# labwiz-module_t420.net
KiCad netlist of a schematic drawn in EAGLE
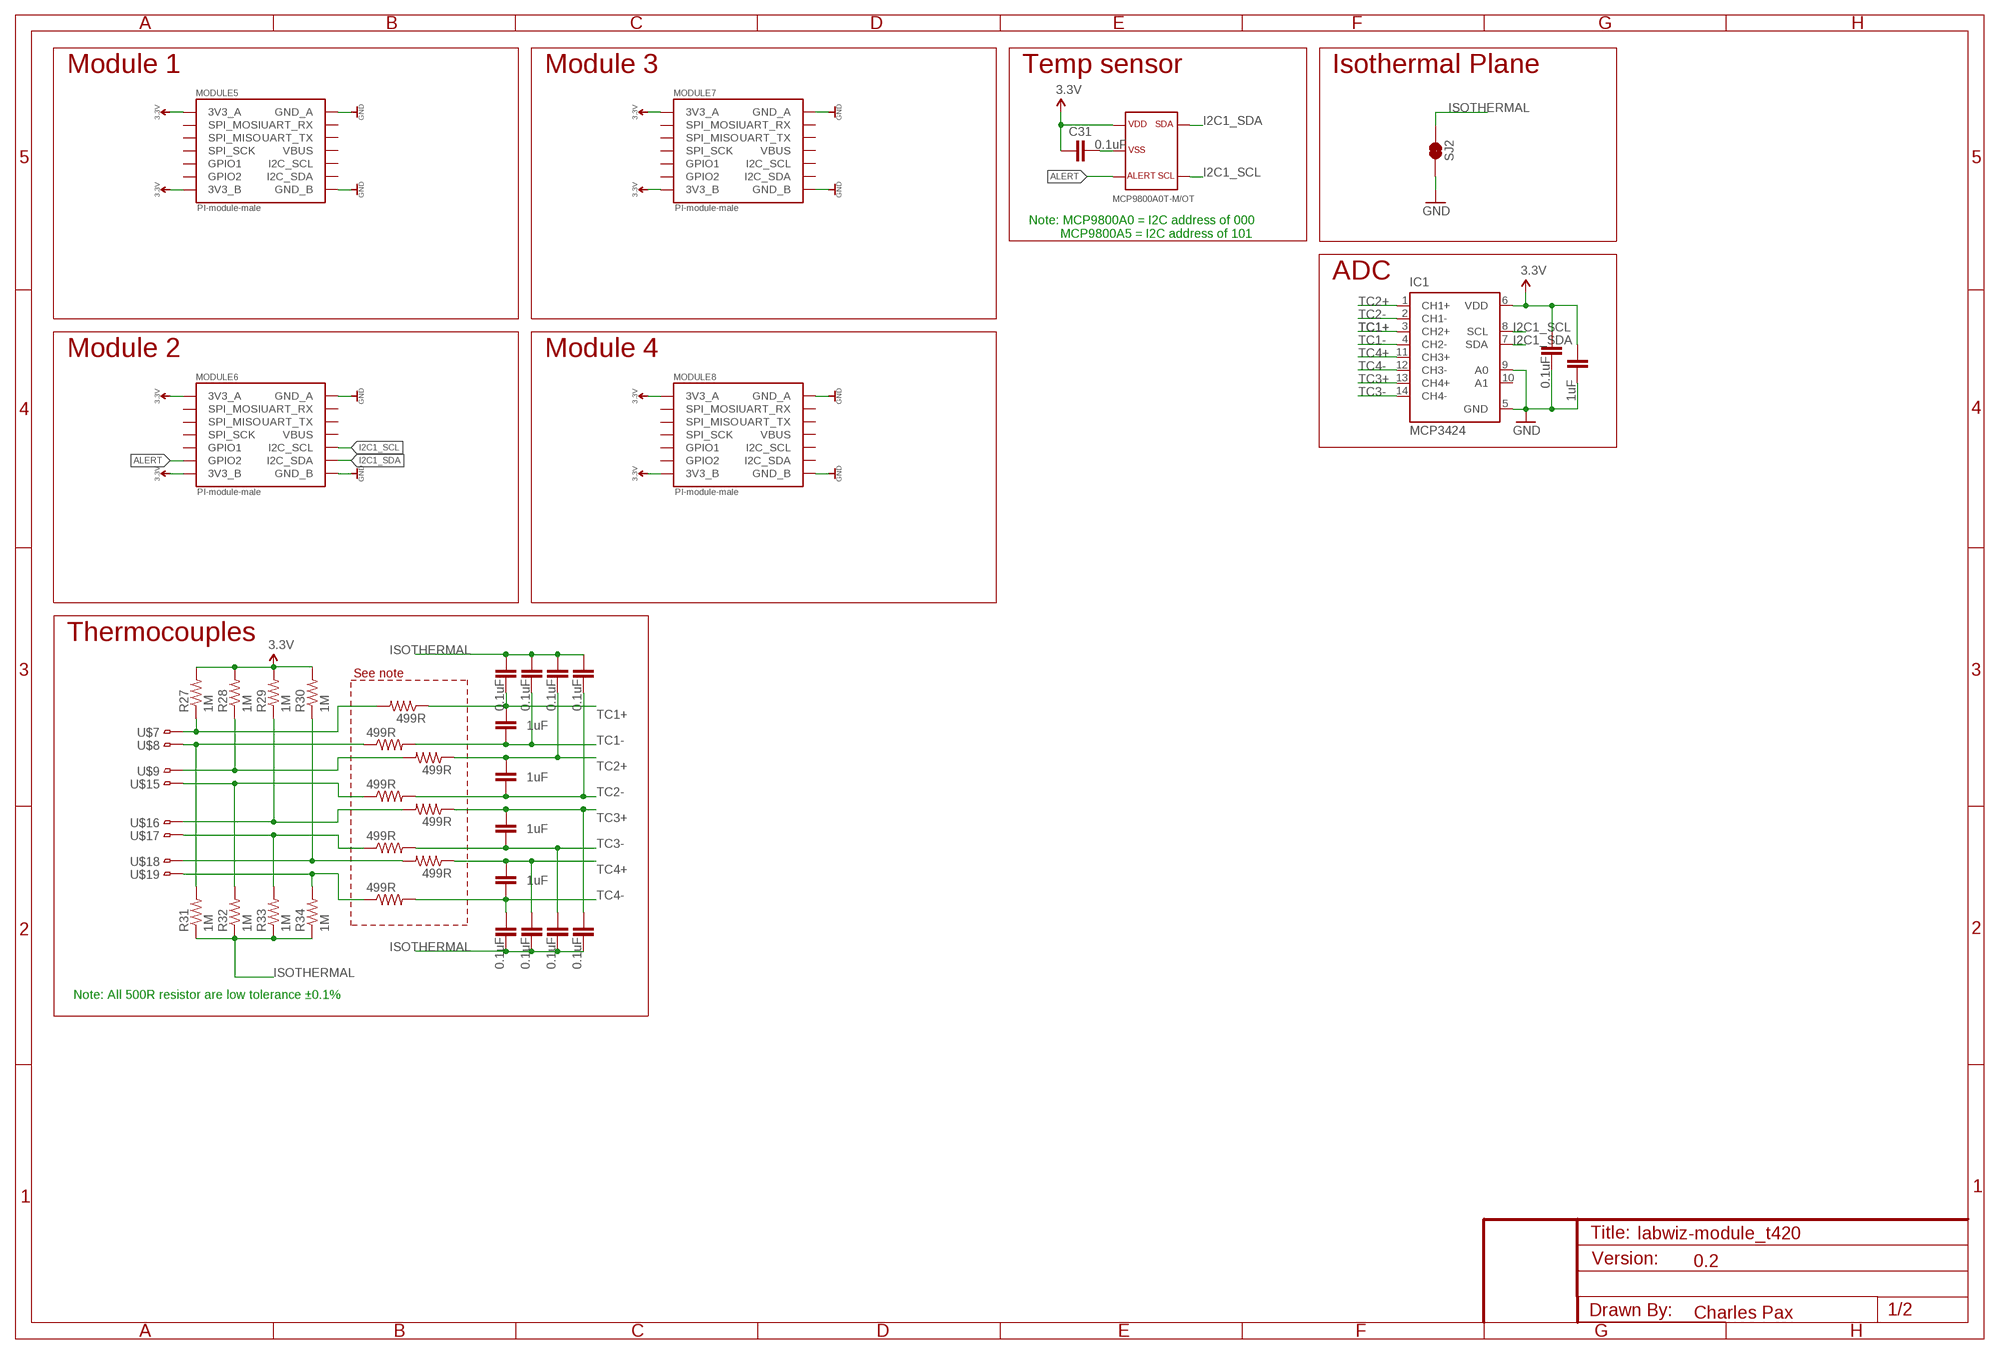
[diagram p0: schematic, sheet 1]

(export (version "E")
  (design (tool "Eeschema 10.0.6"))
  (components
    (comp (ref "C7")
      (value "1uF")
      (footprint "eagle-import:SPARKFUN-CAPACITORS_0603-CAP")
      (libsource (lib "eagle-import") (part "SPARKFUN-CAPACITORS_CAP0603-CAP"))
    )
    (comp (ref "C8")
      (value "1uF")
      (footprint "eagle-import:SPARKFUN-CAPACITORS_0603-CAP")
      (libsource (lib "eagle-import") (part "SPARKFUN-CAPACITORS_CAP0603-CAP"))
    )
    (comp (ref "C10")
      (value "1uF")
      (footprint "eagle-import:SPARKFUN-CAPACITORS_0603-CAP")
      (libsource (lib "eagle-import") (part "SPARKFUN-CAPACITORS_CAP0603-CAP"))
    )
    (comp (ref "C11")
      (value "1uF")
      (footprint "eagle-import:SPARKFUN-CAPACITORS_0603-CAP")
      (libsource (lib "eagle-import") (part "SPARKFUN-CAPACITORS_CAP0603-CAP"))
    )
    (comp (ref "C13")
      (value "0.1uF")
      (footprint "eagle-import:SPARKFUN-CAPACITORS_0603-CAP")
      (libsource (lib "eagle-import") (part "SPARKFUN-CAPACITORS_CAP0603-CAP"))
    )
    (comp (ref "C14")
      (value "0.1uF")
      (footprint "eagle-import:SPARKFUN-CAPACITORS_0603-CAP")
      (libsource (lib "eagle-import") (part "SPARKFUN-CAPACITORS_CAP0603-CAP"))
    )
    (comp (ref "C15")
      (value "0.1uF")
      (footprint "eagle-import:SPARKFUN-CAPACITORS_0603-CAP")
      (libsource (lib "eagle-import") (part "SPARKFUN-CAPACITORS_CAP0603-CAP"))
    )
    (comp (ref "C16")
      (value "0.1uF")
      (footprint "eagle-import:SPARKFUN-CAPACITORS_0603-CAP")
      (libsource (lib "eagle-import") (part "SPARKFUN-CAPACITORS_CAP0603-CAP"))
    )
    (comp (ref "C17")
      (value "0.1uF")
      (footprint "eagle-import:SPARKFUN-CAPACITORS_0603-CAP")
      (libsource (lib "eagle-import") (part "SPARKFUN-CAPACITORS_CAP0603-CAP"))
    )
    (comp (ref "C24")
      (value "0.1uF")
      (footprint "eagle-import:SPARKFUN-CAPACITORS_0603-CAP")
      (libsource (lib "eagle-import") (part "SPARKFUN-CAPACITORS_CAP0603-CAP"))
    )
    (comp (ref "C25")
      (value "0.1uF")
      (footprint "eagle-import:SPARKFUN-CAPACITORS_0603-CAP")
      (libsource (lib "eagle-import") (part "SPARKFUN-CAPACITORS_CAP0603-CAP"))
    )
    (comp (ref "C29")
      (value "0.1uF")
      (footprint "eagle-import:SPARKFUN-CAPACITORS_0603-CAP")
      (libsource (lib "eagle-import") (part "SPARKFUN-CAPACITORS_CAP0603-CAP"))
    )
    (comp (ref "C30")
      (value "1uF")
      (footprint "eagle-import:SPARKFUN-CAPACITORS_0603-CAP")
      (libsource (lib "eagle-import") (part "SPARKFUN-CAPACITORS_CAP0603-CAP"))
    )
    (comp (ref "C31")
      (value "0.1uF")
      (footprint "eagle-import:SPARKFUN-CAPACITORS_0603-CAP")
      (libsource (lib "eagle-import") (part "SPARKFUN-CAPACITORS_CAP0603-CAP"))
    )
    (comp (ref "C37")
      (value "0.1uF")
      (footprint "eagle-import:SPARKFUN-CAPACITORS_0603-CAP")
      (libsource (lib "eagle-import") (part "SPARKFUN-CAPACITORS_CAP0603-CAP"))
    )
    (comp (ref "IC1")
      (value "MCP3424")
      (footprint "eagle-import:SO14")
      (fields (field (name "MF") "Microchip Technology") (field (name "MPN") "MCP3424-E/SL"))
      (libsource (lib "eagle-import") (part "MCP3424"))
    )
    (comp (ref "MODULE5")
      (value "PI-module-male")
      (footprint "eagle-import:M07X2_2MM_EDGE")
      (fields (field (name "MF") "Pax Instruments") (field (name "MPN") "PIxxxx"))
      (libsource (lib "eagle-import") (part "PAX_MODULE_EDGE_MALE_MODULE"))
    )
    (comp (ref "MODULE6")
      (value "PI-module-male")
      (footprint "eagle-import:M07X2_2MM_EDGE")
      (fields (field (name "MF") "Pax Instruments") (field (name "MPN") "PIxxxx"))
      (libsource (lib "eagle-import") (part "PAX_MODULE_EDGE_MALE_MODULE"))
    )
    (comp (ref "MODULE7")
      (value "PI-module-male")
      (footprint "eagle-import:M07X2_2MM_EDGE")
      (fields (field (name "MF") "Pax Instruments") (field (name "MPN") "PIxxxx"))
      (libsource (lib "eagle-import") (part "PAX_MODULE_EDGE_MALE_MODULE"))
    )
    (comp (ref "MODULE8")
      (value "PI-module-male")
      (footprint "eagle-import:M07X2_2MM_EDGE")
      (fields (field (name "MF") "Pax Instruments") (field (name "MPN") "PIxxxx"))
      (libsource (lib "eagle-import") (part "PAX_MODULE_EDGE_MALE_MODULE"))
    )
    (comp (ref "R27")
      (value "1M")
      (footprint "eagle-import:SPARKFUN-RESISTORS_0603-RES")
      (libsource (lib "eagle-import") (part "SPARKFUN-RESISTORS_RESISTOR0603-RES"))
    )
    (comp (ref "R28")
      (value "1M")
      (footprint "eagle-import:SPARKFUN-RESISTORS_0603-RES")
      (libsource (lib "eagle-import") (part "SPARKFUN-RESISTORS_RESISTOR0603-RES"))
    )
    (comp (ref "R29")
      (value "1M")
      (footprint "eagle-import:SPARKFUN-RESISTORS_0603-RES")
      (libsource (lib "eagle-import") (part "SPARKFUN-RESISTORS_RESISTOR0603-RES"))
    )
    (comp (ref "R30")
      (value "1M")
      (footprint "eagle-import:SPARKFUN-RESISTORS_0603-RES")
      (libsource (lib "eagle-import") (part "SPARKFUN-RESISTORS_RESISTOR0603-RES"))
    )
    (comp (ref "R31")
      (value "1M")
      (footprint "eagle-import:SPARKFUN-RESISTORS_0603-RES")
      (libsource (lib "eagle-import") (part "SPARKFUN-RESISTORS_RESISTOR0603-RES"))
    )
    (comp (ref "R32")
      (value "1M")
      (footprint "eagle-import:SPARKFUN-RESISTORS_0603-RES")
      (libsource (lib "eagle-import") (part "SPARKFUN-RESISTORS_RESISTOR0603-RES"))
    )
    (comp (ref "R33")
      (value "1M")
      (footprint "eagle-import:SPARKFUN-RESISTORS_0603-RES")
      (libsource (lib "eagle-import") (part "SPARKFUN-RESISTORS_RESISTOR0603-RES"))
    )
    (comp (ref "R34")
      (value "1M")
      (footprint "eagle-import:SPARKFUN-RESISTORS_0603-RES")
      (libsource (lib "eagle-import") (part "SPARKFUN-RESISTORS_RESISTOR0603-RES"))
    )
    (comp (ref "R35")
      (value "499R")
      (footprint "eagle-import:SPARKFUN-RESISTORS_0603-RES")
      (fields (field (name "MF") "Vishay") (field (name "MPN") "TNPW0603499RBEEA"))
      (libsource (lib "eagle-import") (part "SPARKFUN-RESISTORS_RESISTOR0603-RES"))
    )
    (comp (ref "R36")
      (value "499R")
      (footprint "eagle-import:SPARKFUN-RESISTORS_0603-RES")
      (fields (field (name "MF") "Vishay") (field (name "MPN") "TNPW0603499RBEEA"))
      (libsource (lib "eagle-import") (part "SPARKFUN-RESISTORS_RESISTOR0603-RES"))
    )
    (comp (ref "R37")
      (value "499R")
      (footprint "eagle-import:SPARKFUN-RESISTORS_0603-RES")
      (fields (field (name "MF") "Vishay") (field (name "MPN") "TNPW0603499RBEEA"))
      (libsource (lib "eagle-import") (part "SPARKFUN-RESISTORS_RESISTOR0603-RES"))
    )
    (comp (ref "R38")
      (value "499R")
      (footprint "eagle-import:SPARKFUN-RESISTORS_0603-RES")
      (fields (field (name "MF") "Vishay") (field (name "MPN") "TNPW0603499RBEEA"))
      (libsource (lib "eagle-import") (part "SPARKFUN-RESISTORS_RESISTOR0603-RES"))
    )
    (comp (ref "R39")
      (value "499R")
      (footprint "eagle-import:SPARKFUN-RESISTORS_0603-RES")
      (fields (field (name "MF") "Vishay") (field (name "MPN") "TNPW0603499RBEEA"))
      (libsource (lib "eagle-import") (part "SPARKFUN-RESISTORS_RESISTOR0603-RES"))
    )
    (comp (ref "R40")
      (value "499R")
      (footprint "eagle-import:SPARKFUN-RESISTORS_0603-RES")
      (fields (field (name "MF") "Vishay") (field (name "MPN") "TNPW0603499RBEEA"))
      (libsource (lib "eagle-import") (part "SPARKFUN-RESISTORS_RESISTOR0603-RES"))
    )
    (comp (ref "R41")
      (value "499R")
      (footprint "eagle-import:SPARKFUN-RESISTORS_0603-RES")
      (fields (field (name "MF") "Vishay") (field (name "MPN") "TNPW0603499RBEEA"))
      (libsource (lib "eagle-import") (part "SPARKFUN-RESISTORS_RESISTOR0603-RES"))
    )
    (comp (ref "R42")
      (value "499R")
      (footprint "eagle-import:SPARKFUN-RESISTORS_0603-RES")
      (fields (field (name "MF") "Vishay") (field (name "MPN") "TNPW0603499RBEEA"))
      (libsource (lib "eagle-import") (part "SPARKFUN-RESISTORS_RESISTOR0603-RES"))
    )
    (comp (ref "SJ2")
      (value "JUMPER-PAD-2-NC_BY_TRACE")
      (footprint "eagle-import:PAD-JUMPER-2-NC_BY_TRACE_YES_SILK")
      (libsource (lib "eagle-import") (part "JUMPER-PAD-2-NC_BY_TRACE"))
    )
    (comp (ref "U$7")
      (value "TC-MINI-SINGLE")
      (footprint "eagle-import:TC-CLIP-SINGLE")
      (fields (field (name "MF") "Pax Instrument") (field (name "MPN") "Thermo-clip2"))
      (libsource (lib "eagle-import") (part "TC-MINI-SINGLE"))
    )
    (comp (ref "U$8")
      (value "TC-MINI-SINGLE")
      (footprint "eagle-import:TC-CLIP-SINGLE")
      (fields (field (name "MF") "Pax Instrument") (field (name "MPN") "Thermo-clip2"))
      (libsource (lib "eagle-import") (part "TC-MINI-SINGLE"))
    )
    (comp (ref "U$9")
      (value "TC-MINI-SINGLE")
      (footprint "eagle-import:TC-CLIP-SINGLE")
      (fields (field (name "MF") "Pax Instrument") (field (name "MPN") "Thermo-clip2"))
      (libsource (lib "eagle-import") (part "TC-MINI-SINGLE"))
    )
    (comp (ref "U$15")
      (value "TC-MINI-SINGLE")
      (footprint "eagle-import:TC-CLIP-SINGLE")
      (fields (field (name "MF") "Pax Instrument") (field (name "MPN") "Thermo-clip2"))
      (libsource (lib "eagle-import") (part "TC-MINI-SINGLE"))
    )
    (comp (ref "U$16")
      (value "TC-MINI-SINGLE")
      (footprint "eagle-import:TC-CLIP-SINGLE")
      (fields (field (name "MF") "Pax Instrument") (field (name "MPN") "Thermo-clip2"))
      (libsource (lib "eagle-import") (part "TC-MINI-SINGLE"))
    )
    (comp (ref "U$17")
      (value "TC-MINI-SINGLE")
      (footprint "eagle-import:TC-CLIP-SINGLE")
      (fields (field (name "MF") "Pax Instrument") (field (name "MPN") "Thermo-clip2"))
      (libsource (lib "eagle-import") (part "TC-MINI-SINGLE"))
    )
    (comp (ref "U$18")
      (value "TC-MINI-SINGLE")
      (footprint "eagle-import:TC-CLIP-SINGLE")
      (fields (field (name "MF") "Pax Instrument") (field (name "MPN") "Thermo-clip2"))
      (libsource (lib "eagle-import") (part "TC-MINI-SINGLE"))
    )
    (comp (ref "U$19")
      (value "TC-MINI-SINGLE")
      (footprint "eagle-import:TC-CLIP-SINGLE")
      (fields (field (name "MF") "Pax Instrument") (field (name "MPN") "Thermo-clip2"))
      (libsource (lib "eagle-import") (part "TC-MINI-SINGLE"))
    )
    (comp (ref "U1")
      (value "MCP9800")
      (footprint "eagle-import:SOT23-5L")
      (fields (field (name "MF") "Microchip Technology") (field (name "MPN") "MCP9800A0T-M/OT"))
      (libsource (lib "eagle-import") (part "MCP9800"))
    )
  )
  (nets
    (net (code "1") (name "3.3V") (class "Default")
      (node (ref "C29") (pin "1") (pinfunction "1_1") (pintype "passive"))
      (node (ref "C30") (pin "1") (pinfunction "1_1") (pintype "passive"))
      (node (ref "C31") (pin "1") (pinfunction "1_1") (pintype "passive"))
      (node (ref "IC1") (pin "6") (pinfunction "VDD_6") (pintype "power_in"))
      (node (ref "MODULE5") (pin "P$1") (pinfunction "3V3_B_P$1") (pintype "bidirectional"))
      (node (ref "MODULE5") (pin "P$13") (pinfunction "3V3_A_P$13") (pintype "power_in"))
      (node (ref "MODULE6") (pin "P$1") (pinfunction "3V3_B_P$1") (pintype "bidirectional"))
      (node (ref "MODULE6") (pin "P$13") (pinfunction "3V3_A_P$13") (pintype "power_in"))
      (node (ref "MODULE7") (pin "P$1") (pinfunction "3V3_B_P$1") (pintype "bidirectional"))
      (node (ref "MODULE7") (pin "P$13") (pinfunction "3V3_A_P$13") (pintype "power_in"))
      (node (ref "MODULE8") (pin "P$1") (pinfunction "3V3_B_P$1") (pintype "bidirectional"))
      (node (ref "MODULE8") (pin "P$13") (pinfunction "3V3_A_P$13") (pintype "power_in"))
      (node (ref "R27") (pin "2") (pinfunction "2_2") (pintype "passive"))
      (node (ref "R28") (pin "2") (pinfunction "2_2") (pintype "passive"))
      (node (ref "R29") (pin "2") (pinfunction "2_2") (pintype "passive"))
      (node (ref "R30") (pin "2") (pinfunction "2_2") (pintype "passive"))
      (node (ref "U1") (pin "1") (pinfunction "1_1") (pintype "bidirectional"))
    )
    (net (code "2") (name "ALERT") (class "Default")
      (node (ref "MODULE6") (pin "P$3") (pinfunction "GPIO2_P$3") (pintype "bidirectional"))
      (node (ref "U1") (pin "3") (pinfunction "3_3") (pintype "bidirectional"))
    )
    (net (code "3") (name "GND") (class "Default")
      (node (ref "C29") (pin "2") (pinfunction "2_2") (pintype "passive"))
      (node (ref "C30") (pin "2") (pinfunction "2_2") (pintype "passive"))
      (node (ref "IC1") (pin "5") (pinfunction "GND_5") (pintype "power_in"))
      (node (ref "IC1") (pin "9") (pinfunction "A0_9") (pintype "input"))
      (node (ref "MODULE5") (pin "P$14") (pinfunction "GND_A_P$14") (pintype "power_in"))
      (node (ref "MODULE5") (pin "P$2") (pinfunction "GND_B_P$2") (pintype "bidirectional"))
      (node (ref "MODULE6") (pin "P$14") (pinfunction "GND_A_P$14") (pintype "power_in"))
      (node (ref "MODULE6") (pin "P$2") (pinfunction "GND_B_P$2") (pintype "bidirectional"))
      (node (ref "MODULE7") (pin "P$14") (pinfunction "GND_A_P$14") (pintype "power_in"))
      (node (ref "MODULE7") (pin "P$2") (pinfunction "GND_B_P$2") (pintype "bidirectional"))
      (node (ref "MODULE8") (pin "P$14") (pinfunction "GND_A_P$14") (pintype "power_in"))
      (node (ref "MODULE8") (pin "P$2") (pinfunction "GND_B_P$2") (pintype "bidirectional"))
      (node (ref "SJ2") (pin "1") (pinfunction "1_1") (pintype "passive"))
    )
    (net (code "4") (name "I2C1_SCL") (class "Default")
      (node (ref "IC1") (pin "8") (pinfunction "SCL_8") (pintype "input"))
      (node (ref "MODULE6") (pin "P$6") (pinfunction "I2C_SCL_P$6") (pintype "bidirectional"))
      (node (ref "U1") (pin "4") (pinfunction "4_4") (pintype "bidirectional"))
    )
    (net (code "5") (name "I2C1_SDA") (class "Default")
      (node (ref "IC1") (pin "7") (pinfunction "SDA_7") (pintype "bidirectional"))
      (node (ref "MODULE6") (pin "P$4") (pinfunction "I2C_SDA_P$4") (pintype "bidirectional"))
      (node (ref "U1") (pin "5") (pinfunction "5_5") (pintype "bidirectional"))
    )
    (net (code "6") (name "ISOTHERMAL") (class "Default")
      (node (ref "C13") (pin "2") (pinfunction "2_2") (pintype "passive"))
      (node (ref "C14") (pin "2") (pinfunction "2_2") (pintype "passive"))
      (node (ref "C15") (pin "2") (pinfunction "2_2") (pintype "passive"))
      (node (ref "C16") (pin "2") (pinfunction "2_2") (pintype "passive"))
      (node (ref "C17") (pin "1") (pinfunction "1_1") (pintype "passive"))
      (node (ref "C24") (pin "1") (pinfunction "1_1") (pintype "passive"))
      (node (ref "C25") (pin "1") (pinfunction "1_1") (pintype "passive"))
      (node (ref "C31") (pin "2") (pinfunction "2_2") (pintype "passive"))
      (node (ref "C37") (pin "1") (pinfunction "1_1") (pintype "passive"))
      (node (ref "R31") (pin "1") (pinfunction "1_1") (pintype "passive"))
      (node (ref "R32") (pin "1") (pinfunction "1_1") (pintype "passive"))
      (node (ref "R33") (pin "1") (pinfunction "1_1") (pintype "passive"))
      (node (ref "R34") (pin "1") (pinfunction "1_1") (pintype "passive"))
      (node (ref "SJ2") (pin "2") (pinfunction "2_2") (pintype "passive"))
      (node (ref "U1") (pin "2") (pinfunction "2_2") (pintype "bidirectional"))
    )
    (net (code "7") (name "Net-(U$7-1)") (class "Default")
      (node (ref "R27") (pin "1") (pinfunction "1_1") (pintype "passive"))
      (node (ref "R35") (pin "2") (pinfunction "2_2") (pintype "passive"))
      (node (ref "U$7") (pin "P$1") (pinfunction "1_P$1") (pintype "passive"))
    )
    (net (code "8") (name "Net-(U$8-1)") (class "Default")
      (node (ref "R31") (pin "2") (pinfunction "2_2") (pintype "passive"))
      (node (ref "R36") (pin "1") (pinfunction "1_1") (pintype "passive"))
      (node (ref "U$8") (pin "P$1") (pinfunction "1_P$1") (pintype "passive"))
    )
    (net (code "9") (name "Net-(U$9-1)") (class "Default")
      (node (ref "R28") (pin "1") (pinfunction "1_1") (pintype "passive"))
      (node (ref "R37") (pin "2") (pinfunction "2_2") (pintype "passive"))
      (node (ref "U$9") (pin "P$1") (pinfunction "1_P$1") (pintype "passive"))
    )
    (net (code "10") (name "Net-(U$15-1)") (class "Default")
      (node (ref "R32") (pin "2") (pinfunction "2_2") (pintype "passive"))
      (node (ref "R38") (pin "1") (pinfunction "1_1") (pintype "passive"))
      (node (ref "U$15") (pin "P$1") (pinfunction "1_P$1") (pintype "passive"))
    )
    (net (code "11") (name "Net-(U$16-1)") (class "Default")
      (node (ref "R29") (pin "1") (pinfunction "1_1") (pintype "passive"))
      (node (ref "R39") (pin "2") (pinfunction "2_2") (pintype "passive"))
      (node (ref "U$16") (pin "P$1") (pinfunction "1_P$1") (pintype "passive"))
    )
    (net (code "12") (name "Net-(U$17-1)") (class "Default")
      (node (ref "R33") (pin "2") (pinfunction "2_2") (pintype "passive"))
      (node (ref "R41") (pin "1") (pinfunction "1_1") (pintype "passive"))
      (node (ref "U$17") (pin "P$1") (pinfunction "1_P$1") (pintype "passive"))
    )
    (net (code "13") (name "Net-(U$18-1)") (class "Default")
      (node (ref "R30") (pin "1") (pinfunction "1_1") (pintype "passive"))
      (node (ref "R40") (pin "2") (pinfunction "2_2") (pintype "passive"))
      (node (ref "U$18") (pin "P$1") (pinfunction "1_P$1") (pintype "passive"))
    )
    (net (code "14") (name "Net-(U$19-1)") (class "Default")
      (node (ref "R34") (pin "2") (pinfunction "2_2") (pintype "passive"))
      (node (ref "R42") (pin "1") (pinfunction "1_1") (pintype "passive"))
      (node (ref "U$19") (pin "P$1") (pinfunction "1_P$1") (pintype "passive"))
    )
    (net (code "15") (name "TC1+") (class "Default")
      (node (ref "C17") (pin "2") (pinfunction "2_2") (pintype "passive"))
      (node (ref "C7") (pin "1") (pinfunction "1_1") (pintype "passive"))
      (node (ref "IC1") (pin "3") (pinfunction "CH2+_3") (pintype "input"))
      (node (ref "R35") (pin "1") (pinfunction "1_1") (pintype "passive"))
    )
    (net (code "16") (name "TC1-") (class "Default")
      (node (ref "C24") (pin "2") (pinfunction "2_2") (pintype "passive"))
      (node (ref "C7") (pin "2") (pinfunction "2_2") (pintype "passive"))
      (node (ref "IC1") (pin "4") (pinfunction "CH2-_4") (pintype "input"))
      (node (ref "R36") (pin "2") (pinfunction "2_2") (pintype "passive"))
    )
    (net (code "17") (name "TC2+") (class "Default")
      (node (ref "C25") (pin "2") (pinfunction "2_2") (pintype "passive"))
      (node (ref "C8") (pin "1") (pinfunction "1_1") (pintype "passive"))
      (node (ref "IC1") (pin "1") (pinfunction "CH1+_1") (pintype "input"))
      (node (ref "R37") (pin "1") (pinfunction "1_1") (pintype "passive"))
    )
    (net (code "18") (name "TC2-") (class "Default")
      (node (ref "C37") (pin "2") (pinfunction "2_2") (pintype "passive"))
      (node (ref "C8") (pin "2") (pinfunction "2_2") (pintype "passive"))
      (node (ref "IC1") (pin "2") (pinfunction "CH1-_2") (pintype "input"))
      (node (ref "R38") (pin "2") (pinfunction "2_2") (pintype "passive"))
    )
    (net (code "19") (name "TC3+") (class "Default")
      (node (ref "C10") (pin "1") (pinfunction "1_1") (pintype "passive"))
      (node (ref "C16") (pin "1") (pinfunction "1_1") (pintype "passive"))
      (node (ref "IC1") (pin "13") (pinfunction "CH4+_13") (pintype "input"))
      (node (ref "R39") (pin "1") (pinfunction "1_1") (pintype "passive"))
    )
    (net (code "20") (name "TC3-") (class "Default")
      (node (ref "C10") (pin "2") (pinfunction "2_2") (pintype "passive"))
      (node (ref "C15") (pin "1") (pinfunction "1_1") (pintype "passive"))
      (node (ref "IC1") (pin "14") (pinfunction "CH4-_14") (pintype "input"))
      (node (ref "R41") (pin "2") (pinfunction "2_2") (pintype "passive"))
    )
    (net (code "21") (name "TC4+") (class "Default")
      (node (ref "C11") (pin "1") (pinfunction "1_1") (pintype "passive"))
      (node (ref "C14") (pin "1") (pinfunction "1_1") (pintype "passive"))
      (node (ref "IC1") (pin "11") (pinfunction "CH3+_11") (pintype "input"))
      (node (ref "R40") (pin "1") (pinfunction "1_1") (pintype "passive"))
    )
    (net (code "22") (name "TC4-") (class "Default")
      (node (ref "C11") (pin "2") (pinfunction "2_2") (pintype "passive"))
      (node (ref "C13") (pin "1") (pinfunction "1_1") (pintype "passive"))
      (node (ref "IC1") (pin "12") (pinfunction "CH3-_12") (pintype "input"))
      (node (ref "R42") (pin "2") (pinfunction "2_2") (pintype "passive"))
    )
    (net (code "23") (name "unconnected-(IC1-A1-Pad10)") (class "Default")
      (node (ref "IC1") (pin "10") (pinfunction "A1_10") (pintype "input"))
    )
    (net (code "24") (name "unconnected-(MODULE5-GPIO1-PadP$5)") (class "Default")
      (node (ref "MODULE5") (pin "P$5") (pinfunction "GPIO1_P$5") (pintype "bidirectional"))
    )
    (net (code "25") (name "unconnected-(MODULE5-GPIO2-PadP$3)") (class "Default")
      (node (ref "MODULE5") (pin "P$3") (pinfunction "GPIO2_P$3") (pintype "bidirectional"))
    )
    (net (code "26") (name "unconnected-(MODULE5-I2C_SCL-PadP$6)") (class "Default")
      (node (ref "MODULE5") (pin "P$6") (pinfunction "I2C_SCL_P$6") (pintype "bidirectional"))
    )
    (net (code "27") (name "unconnected-(MODULE5-I2C_SDA-PadP$4)") (class "Default")
      (node (ref "MODULE5") (pin "P$4") (pinfunction "I2C_SDA_P$4") (pintype "bidirectional"))
    )
    (net (code "28") (name "unconnected-(MODULE5-SPI_MISO-PadP$9)") (class "Default")
      (node (ref "MODULE5") (pin "P$9") (pinfunction "SPI_MISO_P$9") (pintype "bidirectional"))
    )
    (net (code "29") (name "unconnected-(MODULE5-SPI_MOSI-PadP$11)") (class "Default")
      (node (ref "MODULE5") (pin "P$11") (pinfunction "SPI_MOSI_P$11") (pintype "bidirectional"))
    )
    (net (code "30") (name "unconnected-(MODULE5-SPI_SCK-PadP$7)") (class "Default")
      (node (ref "MODULE5") (pin "P$7") (pinfunction "SPI_SCK_P$7") (pintype "bidirectional"))
    )
    (net (code "31") (name "unconnected-(MODULE5-UART_RX-PadP$12)") (class "Default")
      (node (ref "MODULE5") (pin "P$12") (pinfunction "UART_RX_P$12") (pintype "bidirectional"))
    )
    (net (code "32") (name "unconnected-(MODULE5-UART_TX-PadP$10)") (class "Default")
      (node (ref "MODULE5") (pin "P$10") (pinfunction "UART_TX_P$10") (pintype "bidirectional"))
    )
    (net (code "33") (name "unconnected-(MODULE5-VBUS-PadP$8)") (class "Default")
      (node (ref "MODULE5") (pin "P$8") (pinfunction "VBUS_P$8") (pintype "bidirectional"))
    )
    (net (code "34") (name "unconnected-(MODULE6-GPIO1-PadP$5)") (class "Default")
      (node (ref "MODULE6") (pin "P$5") (pinfunction "GPIO1_P$5") (pintype "bidirectional"))
    )
    (net (code "35") (name "unconnected-(MODULE6-SPI_MISO-PadP$9)") (class "Default")
      (node (ref "MODULE6") (pin "P$9") (pinfunction "SPI_MISO_P$9") (pintype "bidirectional"))
    )
    (net (code "36") (name "unconnected-(MODULE6-SPI_MOSI-PadP$11)") (class "Default")
      (node (ref "MODULE6") (pin "P$11") (pinfunction "SPI_MOSI_P$11") (pintype "bidirectional"))
    )
    (net (code "37") (name "unconnected-(MODULE6-SPI_SCK-PadP$7)") (class "Default")
      (node (ref "MODULE6") (pin "P$7") (pinfunction "SPI_SCK_P$7") (pintype "bidirectional"))
    )
    (net (code "38") (name "unconnected-(MODULE6-UART_RX-PadP$12)") (class "Default")
      (node (ref "MODULE6") (pin "P$12") (pinfunction "UART_RX_P$12") (pintype "bidirectional"))
    )
    (net (code "39") (name "unconnected-(MODULE6-UART_TX-PadP$10)") (class "Default")
      (node (ref "MODULE6") (pin "P$10") (pinfunction "UART_TX_P$10") (pintype "bidirectional"))
    )
    (net (code "40") (name "unconnected-(MODULE6-VBUS-PadP$8)") (class "Default")
      (node (ref "MODULE6") (pin "P$8") (pinfunction "VBUS_P$8") (pintype "bidirectional"))
    )
    (net (code "41") (name "unconnected-(MODULE7-GPIO1-PadP$5)") (class "Default")
      (node (ref "MODULE7") (pin "P$5") (pinfunction "GPIO1_P$5") (pintype "bidirectional"))
    )
    (net (code "42") (name "unconnected-(MODULE7-GPIO2-PadP$3)") (class "Default")
      (node (ref "MODULE7") (pin "P$3") (pinfunction "GPIO2_P$3") (pintype "bidirectional"))
    )
    (net (code "43") (name "unconnected-(MODULE7-I2C_SCL-PadP$6)") (class "Default")
      (node (ref "MODULE7") (pin "P$6") (pinfunction "I2C_SCL_P$6") (pintype "bidirectional"))
    )
    (net (code "44") (name "unconnected-(MODULE7-I2C_SDA-PadP$4)") (class "Default")
      (node (ref "MODULE7") (pin "P$4") (pinfunction "I2C_SDA_P$4") (pintype "bidirectional"))
    )
    (net (code "45") (name "unconnected-(MODULE7-SPI_MISO-PadP$9)") (class "Default")
      (node (ref "MODULE7") (pin "P$9") (pinfunction "SPI_MISO_P$9") (pintype "bidirectional"))
    )
    (net (code "46") (name "unconnected-(MODULE7-SPI_MOSI-PadP$11)") (class "Default")
      (node (ref "MODULE7") (pin "P$11") (pinfunction "SPI_MOSI_P$11") (pintype "bidirectional"))
    )
    (net (code "47") (name "unconnected-(MODULE7-SPI_SCK-PadP$7)") (class "Default")
      (node (ref "MODULE7") (pin "P$7") (pinfunction "SPI_SCK_P$7") (pintype "bidirectional"))
    )
    (net (code "48") (name "unconnected-(MODULE7-UART_RX-PadP$12)") (class "Default")
      (node (ref "MODULE7") (pin "P$12") (pinfunction "UART_RX_P$12") (pintype "bidirectional"))
    )
    (net (code "49") (name "unconnected-(MODULE7-UART_TX-PadP$10)") (class "Default")
      (node (ref "MODULE7") (pin "P$10") (pinfunction "UART_TX_P$10") (pintype "bidirectional"))
    )
    (net (code "50") (name "unconnected-(MODULE7-VBUS-PadP$8)") (class "Default")
      (node (ref "MODULE7") (pin "P$8") (pinfunction "VBUS_P$8") (pintype "bidirectional"))
    )
    (net (code "51") (name "unconnected-(MODULE8-GPIO1-PadP$5)") (class "Default")
      (node (ref "MODULE8") (pin "P$5") (pinfunction "GPIO1_P$5") (pintype "bidirectional"))
    )
    (net (code "52") (name "unconnected-(MODULE8-GPIO2-PadP$3)") (class "Default")
      (node (ref "MODULE8") (pin "P$3") (pinfunction "GPIO2_P$3") (pintype "bidirectional"))
    )
    (net (code "53") (name "unconnected-(MODULE8-I2C_SCL-PadP$6)") (class "Default")
      (node (ref "MODULE8") (pin "P$6") (pinfunction "I2C_SCL_P$6") (pintype "bidirectional"))
    )
    (net (code "54") (name "unconnected-(MODULE8-I2C_SDA-PadP$4)") (class "Default")
      (node (ref "MODULE8") (pin "P$4") (pinfunction "I2C_SDA_P$4") (pintype "bidirectional"))
    )
    (net (code "55") (name "unconnected-(MODULE8-SPI_MISO-PadP$9)") (class "Default")
      (node (ref "MODULE8") (pin "P$9") (pinfunction "SPI_MISO_P$9") (pintype "bidirectional"))
    )
    (net (code "56") (name "unconnected-(MODULE8-SPI_MOSI-PadP$11)") (class "Default")
      (node (ref "MODULE8") (pin "P$11") (pinfunction "SPI_MOSI_P$11") (pintype "bidirectional"))
    )
    (net (code "57") (name "unconnected-(MODULE8-SPI_SCK-PadP$7)") (class "Default")
      (node (ref "MODULE8") (pin "P$7") (pinfunction "SPI_SCK_P$7") (pintype "bidirectional"))
    )
    (net (code "58") (name "unconnected-(MODULE8-UART_RX-PadP$12)") (class "Default")
      (node (ref "MODULE8") (pin "P$12") (pinfunction "UART_RX_P$12") (pintype "bidirectional"))
    )
    (net (code "59") (name "unconnected-(MODULE8-UART_TX-PadP$10)") (class "Default")
      (node (ref "MODULE8") (pin "P$10") (pinfunction "UART_TX_P$10") (pintype "bidirectional"))
    )
    (net (code "60") (name "unconnected-(MODULE8-VBUS-PadP$8)") (class "Default")
      (node (ref "MODULE8") (pin "P$8") (pinfunction "VBUS_P$8") (pintype "bidirectional"))
    )
  )
)
